# PX4FMUv2_4_6_01.net
KiCad netlist of a schematic drawn in Altium Designer
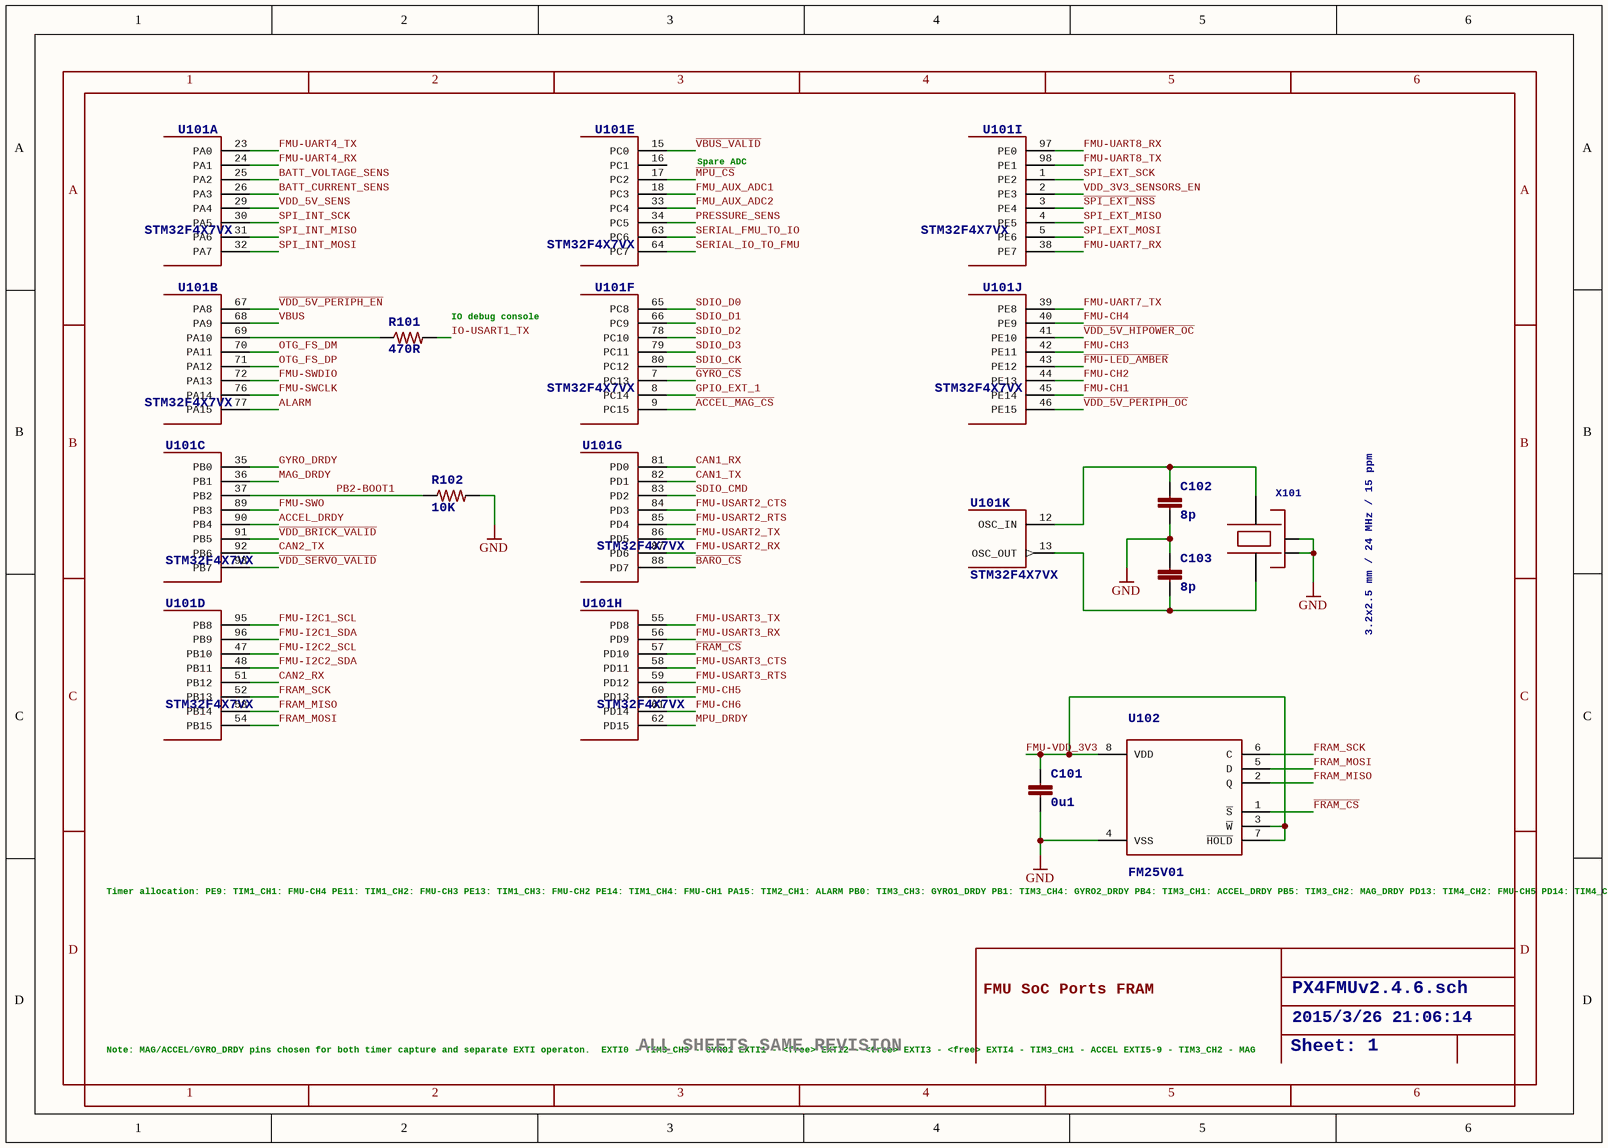
[diagram p0: PX4FMUv2.4.6_01.SchDoc]

(export (version "E")
  (design (tool "Eeschema 10.0.6"))
  (components
    (comp (ref "C101")
      (value "0u1")
      (footprint "0402-CAP")
      (description "<b>Capacitor</b>\nStandard 0603 ceramic capacitor, and 0.1\" leaded capacitor.")
      (fields (field (name "PARTNO") "CC0402ZRY5V7BB104"))
      (libsource (lib "pixhawk2") (part "CAP0402"))
    )
    (comp (ref "C102")
      (value "8p")
      (footprint "0402-CAP")
      (description "<b>Capacitor</b>\nStandard 0603 ceramic capacitor, and 0.1\" leaded capacitor.")
      (fields (field (name "PARTNO") "C1005C0G1H080C"))
      (libsource (lib "pixhawk2") (part "CAP0402"))
    )
    (comp (ref "C103")
      (value "8p")
      (footprint "0402-CAP")
      (description "<b>Capacitor</b>\nStandard 0603 ceramic capacitor, and 0.1\" leaded capacitor.")
      (fields (field (name "PARTNO") "C1005C0G1H080C"))
      (libsource (lib "pixhawk2") (part "CAP0402"))
    )
    (comp (ref "R101")
      (value "470R")
      (footprint "0402-RES")
      (fields (field (name "PARTNO") "RC0402FR-07470RL"))
      (libsource (lib "pixhawk2") (part "RESISTOR0402-RES"))
    )
    (comp (ref "R102")
      (value "10K")
      (footprint "0402-RES")
      (fields (field (name "PARTNO") "RC0402FR-0710KL"))
      (libsource (lib "pixhawk2") (part "RESISTOR0402-RES"))
    )
    (comp (ref "U101")
      (value "STM32F4X7VX")
      (footprint "TQFP100")
      (fields (field (name "PARTNO") "STM32F427VI"))
      (libsource (lib "pixhawk2") (part "STM32F4X7VX"))
    )
    (comp (ref "U102")
      (value "FM25V01")
      (footprint "SO08")
      (description "<b>FM25V01 128Kb Serial 3V F-RAM Memory</b>")
      (fields (field (name "PARTNO") "FM25V01-G"))
      (libsource (lib "pixhawk2") (part "FM25V01"))
    )
    (comp (ref "X101")
      (value "3.2x2.5 mm / 24 MHz / 15 ppm")
      (footprint "OSCILLATOR-3.2X2.5")
      (description "Crystal Oscillator in 3.2x2.5 SMD")
      (libsource (lib "pixhawk2") (part "OSCILLATOR-3.2X2.5"))
    )
  )
  (nets
    (net (code "1") (name "/ACCEL_DRDY") (class "Default")
      (node (ref "U101") (pin "90") (pinfunction "PB4_90") (pintype "passive"))
    )
    (net (code "2") (name "/ALARM") (class "Default")
      (node (ref "U101") (pin "77") (pinfunction "PA15_77") (pintype "passive"))
    )
    (net (code "3") (name "/BATT_CURRENT_SENS") (class "Default")
      (node (ref "U101") (pin "26") (pinfunction "PA3_26") (pintype "passive"))
    )
    (net (code "4") (name "/BATT_VOLTAGE_SENS") (class "Default")
      (node (ref "U101") (pin "25") (pinfunction "PA2_25") (pintype "passive"))
    )
    (net (code "5") (name "/CAN1_RX") (class "Default")
      (node (ref "U101") (pin "81") (pinfunction "PD0_81") (pintype "passive"))
    )
    (net (code "6") (name "/CAN1_TX") (class "Default")
      (node (ref "U101") (pin "82") (pinfunction "PD1_82") (pintype "passive"))
    )
    (net (code "7") (name "/CAN2_RX") (class "Default")
      (node (ref "U101") (pin "51") (pinfunction "PB12_51") (pintype "passive"))
    )
    (net (code "8") (name "/CAN2_TX") (class "Default")
      (node (ref "U101") (pin "92") (pinfunction "PB6_92") (pintype "passive"))
    )
    (net (code "9") (name "/FMU-CH1") (class "Default")
      (node (ref "U101") (pin "45") (pinfunction "PE14_45") (pintype "passive"))
    )
    (net (code "10") (name "/FMU-CH2") (class "Default")
      (node (ref "U101") (pin "44") (pinfunction "PE13_44") (pintype "passive"))
    )
    (net (code "11") (name "/FMU-CH3") (class "Default")
      (node (ref "U101") (pin "42") (pinfunction "PE11_42") (pintype "passive"))
    )
    (net (code "12") (name "/FMU-CH4") (class "Default")
      (node (ref "U101") (pin "40") (pinfunction "PE9_40") (pintype "passive"))
    )
    (net (code "13") (name "/FMU-CH5") (class "Default")
      (node (ref "U101") (pin "60") (pinfunction "PD13_60") (pintype "passive"))
    )
    (net (code "14") (name "/FMU-CH6") (class "Default")
      (node (ref "U101") (pin "61") (pinfunction "PD14_61") (pintype "passive"))
    )
    (net (code "15") (name "/FMU-I2C1_SCL") (class "Default")
      (node (ref "U101") (pin "95") (pinfunction "PB8_95") (pintype "passive"))
    )
    (net (code "16") (name "/FMU-I2C1_SDA") (class "Default")
      (node (ref "U101") (pin "96") (pinfunction "PB9_96") (pintype "passive"))
    )
    (net (code "17") (name "/FMU-I2C2_SCL") (class "Default")
      (node (ref "U101") (pin "47") (pinfunction "PB10_47") (pintype "passive"))
    )
    (net (code "18") (name "/FMU-I2C2_SDA") (class "Default")
      (node (ref "U101") (pin "48") (pinfunction "PB11_48") (pintype "passive"))
    )
    (net (code "19") (name "/FMU-SWCLK") (class "Default")
      (node (ref "U101") (pin "76") (pinfunction "PA14_76") (pintype "passive"))
    )
    (net (code "20") (name "/FMU-SWDIO") (class "Default")
      (node (ref "U101") (pin "72") (pinfunction "PA13_72") (pintype "passive"))
    )
    (net (code "21") (name "/FMU-SWO") (class "Default")
      (node (ref "U101") (pin "89") (pinfunction "PB3_89") (pintype "passive"))
    )
    (net (code "22") (name "/FMU-UART4_RX") (class "Default")
      (node (ref "U101") (pin "24") (pinfunction "PA1_24") (pintype "passive"))
    )
    (net (code "23") (name "/FMU-UART4_TX") (class "Default")
      (node (ref "U101") (pin "23") (pinfunction "PA0_23") (pintype "passive"))
    )
    (net (code "24") (name "/FMU-UART7_RX") (class "Default")
      (node (ref "U101") (pin "38") (pinfunction "PE7_38") (pintype "passive"))
    )
    (net (code "25") (name "/FMU-UART7_TX") (class "Default")
      (node (ref "U101") (pin "39") (pinfunction "PE8_39") (pintype "passive"))
    )
    (net (code "26") (name "/FMU-UART8_RX") (class "Default")
      (node (ref "U101") (pin "97") (pinfunction "PE0_97") (pintype "passive"))
    )
    (net (code "27") (name "/FMU-UART8_TX") (class "Default")
      (node (ref "U101") (pin "98") (pinfunction "PE1_98") (pintype "passive"))
    )
    (net (code "28") (name "/FMU-USART2_CTS") (class "Default")
      (node (ref "U101") (pin "84") (pinfunction "PD3_84") (pintype "passive"))
    )
    (net (code "29") (name "/FMU-USART2_RTS") (class "Default")
      (node (ref "U101") (pin "85") (pinfunction "PD4_85") (pintype "passive"))
    )
    (net (code "30") (name "/FMU-USART2_RX") (class "Default")
      (node (ref "U101") (pin "87") (pinfunction "PD6_87") (pintype "passive"))
    )
    (net (code "31") (name "/FMU-USART2_TX") (class "Default")
      (node (ref "U101") (pin "86") (pinfunction "PD5_86") (pintype "passive"))
    )
    (net (code "32") (name "/FMU-USART3_CTS") (class "Default")
      (node (ref "U101") (pin "58") (pinfunction "PD11_58") (pintype "passive"))
    )
    (net (code "33") (name "/FMU-USART3_RTS") (class "Default")
      (node (ref "U101") (pin "59") (pinfunction "PD12_59") (pintype "passive"))
    )
    (net (code "34") (name "/FMU-USART3_RX") (class "Default")
      (node (ref "U101") (pin "56") (pinfunction "PD9_56") (pintype "passive"))
    )
    (net (code "35") (name "/FMU-USART3_TX") (class "Default")
      (node (ref "U101") (pin "55") (pinfunction "PD8_55") (pintype "passive"))
    )
    (net (code "36") (name "/FMU-VDD_3V3") (class "Default")
      (node (ref "C101") (pin "P$1") (pinfunction "1_P$1") (pintype "passive"))
      (node (ref "U102") (pin "3") (pinfunction "~{W}_3") (pintype "passive"))
      (node (ref "U102") (pin "7") (pinfunction "~{HOLD}_7") (pintype "passive"))
      (node (ref "U102") (pin "8") (pinfunction "VDD_8") (pintype "passive"))
    )
    (net (code "37") (name "/FMU_AUX_ADC1") (class "Default")
      (node (ref "U101") (pin "18") (pinfunction "PC3_18") (pintype "passive"))
    )
    (net (code "38") (name "/FMU_AUX_ADC2") (class "Default")
      (node (ref "U101") (pin "33") (pinfunction "PC4_33") (pintype "passive"))
    )
    (net (code "39") (name "/FRAM_MISO") (class "Default")
      (node (ref "U101") (pin "53") (pinfunction "PB14_53") (pintype "passive"))
      (node (ref "U102") (pin "2") (pinfunction "Q_2") (pintype "passive"))
    )
    (net (code "40") (name "/FRAM_MOSI") (class "Default")
      (node (ref "U101") (pin "54") (pinfunction "PB15_54") (pintype "passive"))
      (node (ref "U102") (pin "5") (pinfunction "D_5") (pintype "passive"))
    )
    (net (code "41") (name "/FRAM_SCK") (class "Default")
      (node (ref "U101") (pin "52") (pinfunction "PB13_52") (pintype "passive"))
      (node (ref "U102") (pin "6") (pinfunction "C_6") (pintype "passive"))
    )
    (net (code "42") (name "/GPIO_EXT_1") (class "Default")
      (node (ref "U101") (pin "8") (pinfunction "PC14_8") (pintype "passive"))
    )
    (net (code "43") (name "/GYRO_DRDY") (class "Default")
      (node (ref "U101") (pin "35") (pinfunction "PB0_35") (pintype "passive"))
    )
    (net (code "44") (name "/IO-USART1_TX") (class "Default")
      (node (ref "R101") (pin "P$2") (pinfunction "2_P$2") (pintype "passive"))
    )
    (net (code "45") (name "/MAG_DRDY") (class "Default")
      (node (ref "U101") (pin "36") (pinfunction "PB1_36") (pintype "passive"))
    )
    (net (code "46") (name "/MPU_DRDY") (class "Default")
      (node (ref "U101") (pin "62") (pinfunction "PD15_62") (pintype "passive"))
    )
    (net (code "47") (name "/OTG_FS_DM") (class "Default")
      (node (ref "U101") (pin "70") (pinfunction "PA11_70") (pintype "passive"))
    )
    (net (code "48") (name "/OTG_FS_DP") (class "Default")
      (node (ref "U101") (pin "71") (pinfunction "PA12_71") (pintype "passive"))
    )
    (net (code "49") (name "/PB2-BOOT1") (class "Default")
      (node (ref "R102") (pin "P$1") (pinfunction "1_P$1") (pintype "passive"))
      (node (ref "U101") (pin "37") (pinfunction "PB2_37") (pintype "passive"))
    )
    (net (code "50") (name "/PRESSURE_SENS") (class "Default")
      (node (ref "U101") (pin "34") (pinfunction "PC5_34") (pintype "passive"))
    )
    (net (code "51") (name "/SDIO_CK") (class "Default")
      (node (ref "U101") (pin "80") (pinfunction "PC12_80") (pintype "passive"))
    )
    (net (code "52") (name "/SDIO_CMD") (class "Default")
      (node (ref "U101") (pin "83") (pinfunction "PD2_83") (pintype "passive"))
    )
    (net (code "53") (name "/SDIO_D0") (class "Default")
      (node (ref "U101") (pin "65") (pinfunction "PC8_65") (pintype "passive"))
    )
    (net (code "54") (name "/SDIO_D1") (class "Default")
      (node (ref "U101") (pin "66") (pinfunction "PC9_66") (pintype "passive"))
    )
    (net (code "55") (name "/SDIO_D2") (class "Default")
      (node (ref "U101") (pin "78") (pinfunction "PC10_78") (pintype "passive"))
    )
    (net (code "56") (name "/SDIO_D3") (class "Default")
      (node (ref "U101") (pin "79") (pinfunction "PC11_79") (pintype "passive"))
    )
    (net (code "57") (name "/SERIAL_FMU_TO_IO") (class "Default")
      (node (ref "U101") (pin "63") (pinfunction "PC6_63") (pintype "passive"))
    )
    (net (code "58") (name "/SERIAL_IO_TO_FMU") (class "Default")
      (node (ref "U101") (pin "64") (pinfunction "PC7_64") (pintype "passive"))
    )
    (net (code "59") (name "/SPI_EXT_MISO") (class "Default")
      (node (ref "U101") (pin "4") (pinfunction "PE5_4") (pintype "passive"))
    )
    (net (code "60") (name "/SPI_EXT_MOSI") (class "Default")
      (node (ref "U101") (pin "5") (pinfunction "PE6_5") (pintype "passive"))
    )
    (net (code "61") (name "/SPI_EXT_SCK") (class "Default")
      (node (ref "U101") (pin "1") (pinfunction "PE2_1") (pintype "passive"))
    )
    (net (code "62") (name "/SPI_INT_MISO") (class "Default")
      (node (ref "U101") (pin "31") (pinfunction "PA6_31") (pintype "passive"))
    )
    (net (code "63") (name "/SPI_INT_MOSI") (class "Default")
      (node (ref "U101") (pin "32") (pinfunction "PA7_32") (pintype "passive"))
    )
    (net (code "64") (name "/SPI_INT_SCK") (class "Default")
      (node (ref "U101") (pin "30") (pinfunction "PA5_30") (pintype "passive"))
    )
    (net (code "65") (name "/VBUS") (class "Default")
      (node (ref "U101") (pin "68") (pinfunction "PA9_68") (pintype "passive"))
    )
    (net (code "66") (name "/VDD_3V3_SENSORS_EN") (class "Default")
      (node (ref "U101") (pin "2") (pinfunction "PE3_2") (pintype "passive"))
    )
    (net (code "67") (name "/VDD_5V_SENS") (class "Default")
      (node (ref "U101") (pin "29") (pinfunction "PA4_29") (pintype "passive"))
    )
    (net (code "68") (name "/~{ACCEL_MAG_CS}") (class "Default")
      (node (ref "U101") (pin "9") (pinfunction "PC15_9") (pintype "passive"))
    )
    (net (code "69") (name "/~{BARO_CS}") (class "Default")
      (node (ref "U101") (pin "88") (pinfunction "PD7_88") (pintype "passive"))
    )
    (net (code "70") (name "/~{FMU-LED_AMBER}") (class "Default")
      (node (ref "U101") (pin "43") (pinfunction "PE12_43") (pintype "passive"))
    )
    (net (code "71") (name "/~{FRAM_CS}") (class "Default")
      (node (ref "U101") (pin "57") (pinfunction "PD10_57") (pintype "passive"))
      (node (ref "U102") (pin "1") (pinfunction "~{S}_1") (pintype "passive"))
    )
    (net (code "72") (name "/~{GYRO_CS}") (class "Default")
      (node (ref "U101") (pin "7") (pinfunction "PC13_7") (pintype "passive"))
    )
    (net (code "73") (name "/~{MPU_CS}") (class "Default")
      (node (ref "U101") (pin "17") (pinfunction "PC2_17") (pintype "passive"))
    )
    (net (code "74") (name "/~{SPI_EXT_NSS}") (class "Default")
      (node (ref "U101") (pin "3") (pinfunction "PE4_3") (pintype "passive"))
    )
    (net (code "75") (name "/~{VBUS_VALID}") (class "Default")
      (node (ref "U101") (pin "15") (pinfunction "PC0_15") (pintype "passive"))
    )
    (net (code "76") (name "/~{VDD_5V_HIPOWER_OC}") (class "Default")
      (node (ref "U101") (pin "41") (pinfunction "PE10_41") (pintype "passive"))
    )
    (net (code "77") (name "/~{VDD_5V_PERIPH_EN}") (class "Default")
      (node (ref "U101") (pin "67") (pinfunction "PA8_67") (pintype "passive"))
    )
    (net (code "78") (name "/~{VDD_5V_PERIPH_OC}") (class "Default")
      (node (ref "U101") (pin "46") (pinfunction "PE15_46") (pintype "passive"))
    )
    (net (code "79") (name "/~{VDD_BRICK_VALID}") (class "Default")
      (node (ref "U101") (pin "91") (pinfunction "PB5_91") (pintype "passive"))
    )
    (net (code "80") (name "/~{VDD_SERVO_VALID}") (class "Default")
      (node (ref "U101") (pin "93") (pinfunction "PB7_93") (pintype "passive"))
    )
    (net (code "81") (name "GND") (class "Default")
      (node (ref "C101") (pin "P$2") (pinfunction "2_P$2") (pintype "passive"))
      (node (ref "C102") (pin "P$2") (pinfunction "2_P$2") (pintype "passive"))
      (node (ref "C103") (pin "P$1") (pinfunction "1_P$1") (pintype "passive"))
      (node (ref "R102") (pin "P$2") (pinfunction "2_P$2") (pintype "passive"))
      (node (ref "U102") (pin "4") (pinfunction "VSS_4") (pintype "passive"))
      (node (ref "X101") (pin "2") (pinfunction "NC_2_2") (pintype "open_emitter"))
      (node (ref "X101") (pin "4") (pinfunction "NC_4_4") (pintype "open_emitter"))
    )
    (net (code "82") (name "Net-(C102-1)") (class "Default")
      (node (ref "C102") (pin "P$1") (pinfunction "1_P$1") (pintype "passive"))
      (node (ref "U101") (pin "12") (pinfunction "OSC_IN_12") (pintype "passive"))
      (node (ref "X101") (pin "3") (pinfunction "3_3") (pintype "passive"))
    )
    (net (code "83") (name "Net-(C103-2)") (class "Default")
      (node (ref "C103") (pin "P$2") (pinfunction "2_P$2") (pintype "passive"))
      (node (ref "U101") (pin "13") (pinfunction "OSC_OUT_13") (pintype "output"))
      (node (ref "X101") (pin "1") (pinfunction "1_1") (pintype "passive"))
    )
    (net (code "84") (name "Net-(R101-1)") (class "Default")
      (node (ref "R101") (pin "P$1") (pinfunction "1_P$1") (pintype "passive"))
      (node (ref "U101") (pin "69") (pinfunction "PA10_69") (pintype "passive"))
    )
    (net (code "85") (name "unconnected-(U101E-PC1-Pad16)") (class "Default")
      (node (ref "U101") (pin "16") (pinfunction "PC1_16") (pintype "passive"))
    )
  )
)
